# Pico-CRSF.net
KiCad netlist of a schematic drawn in Altium Designer
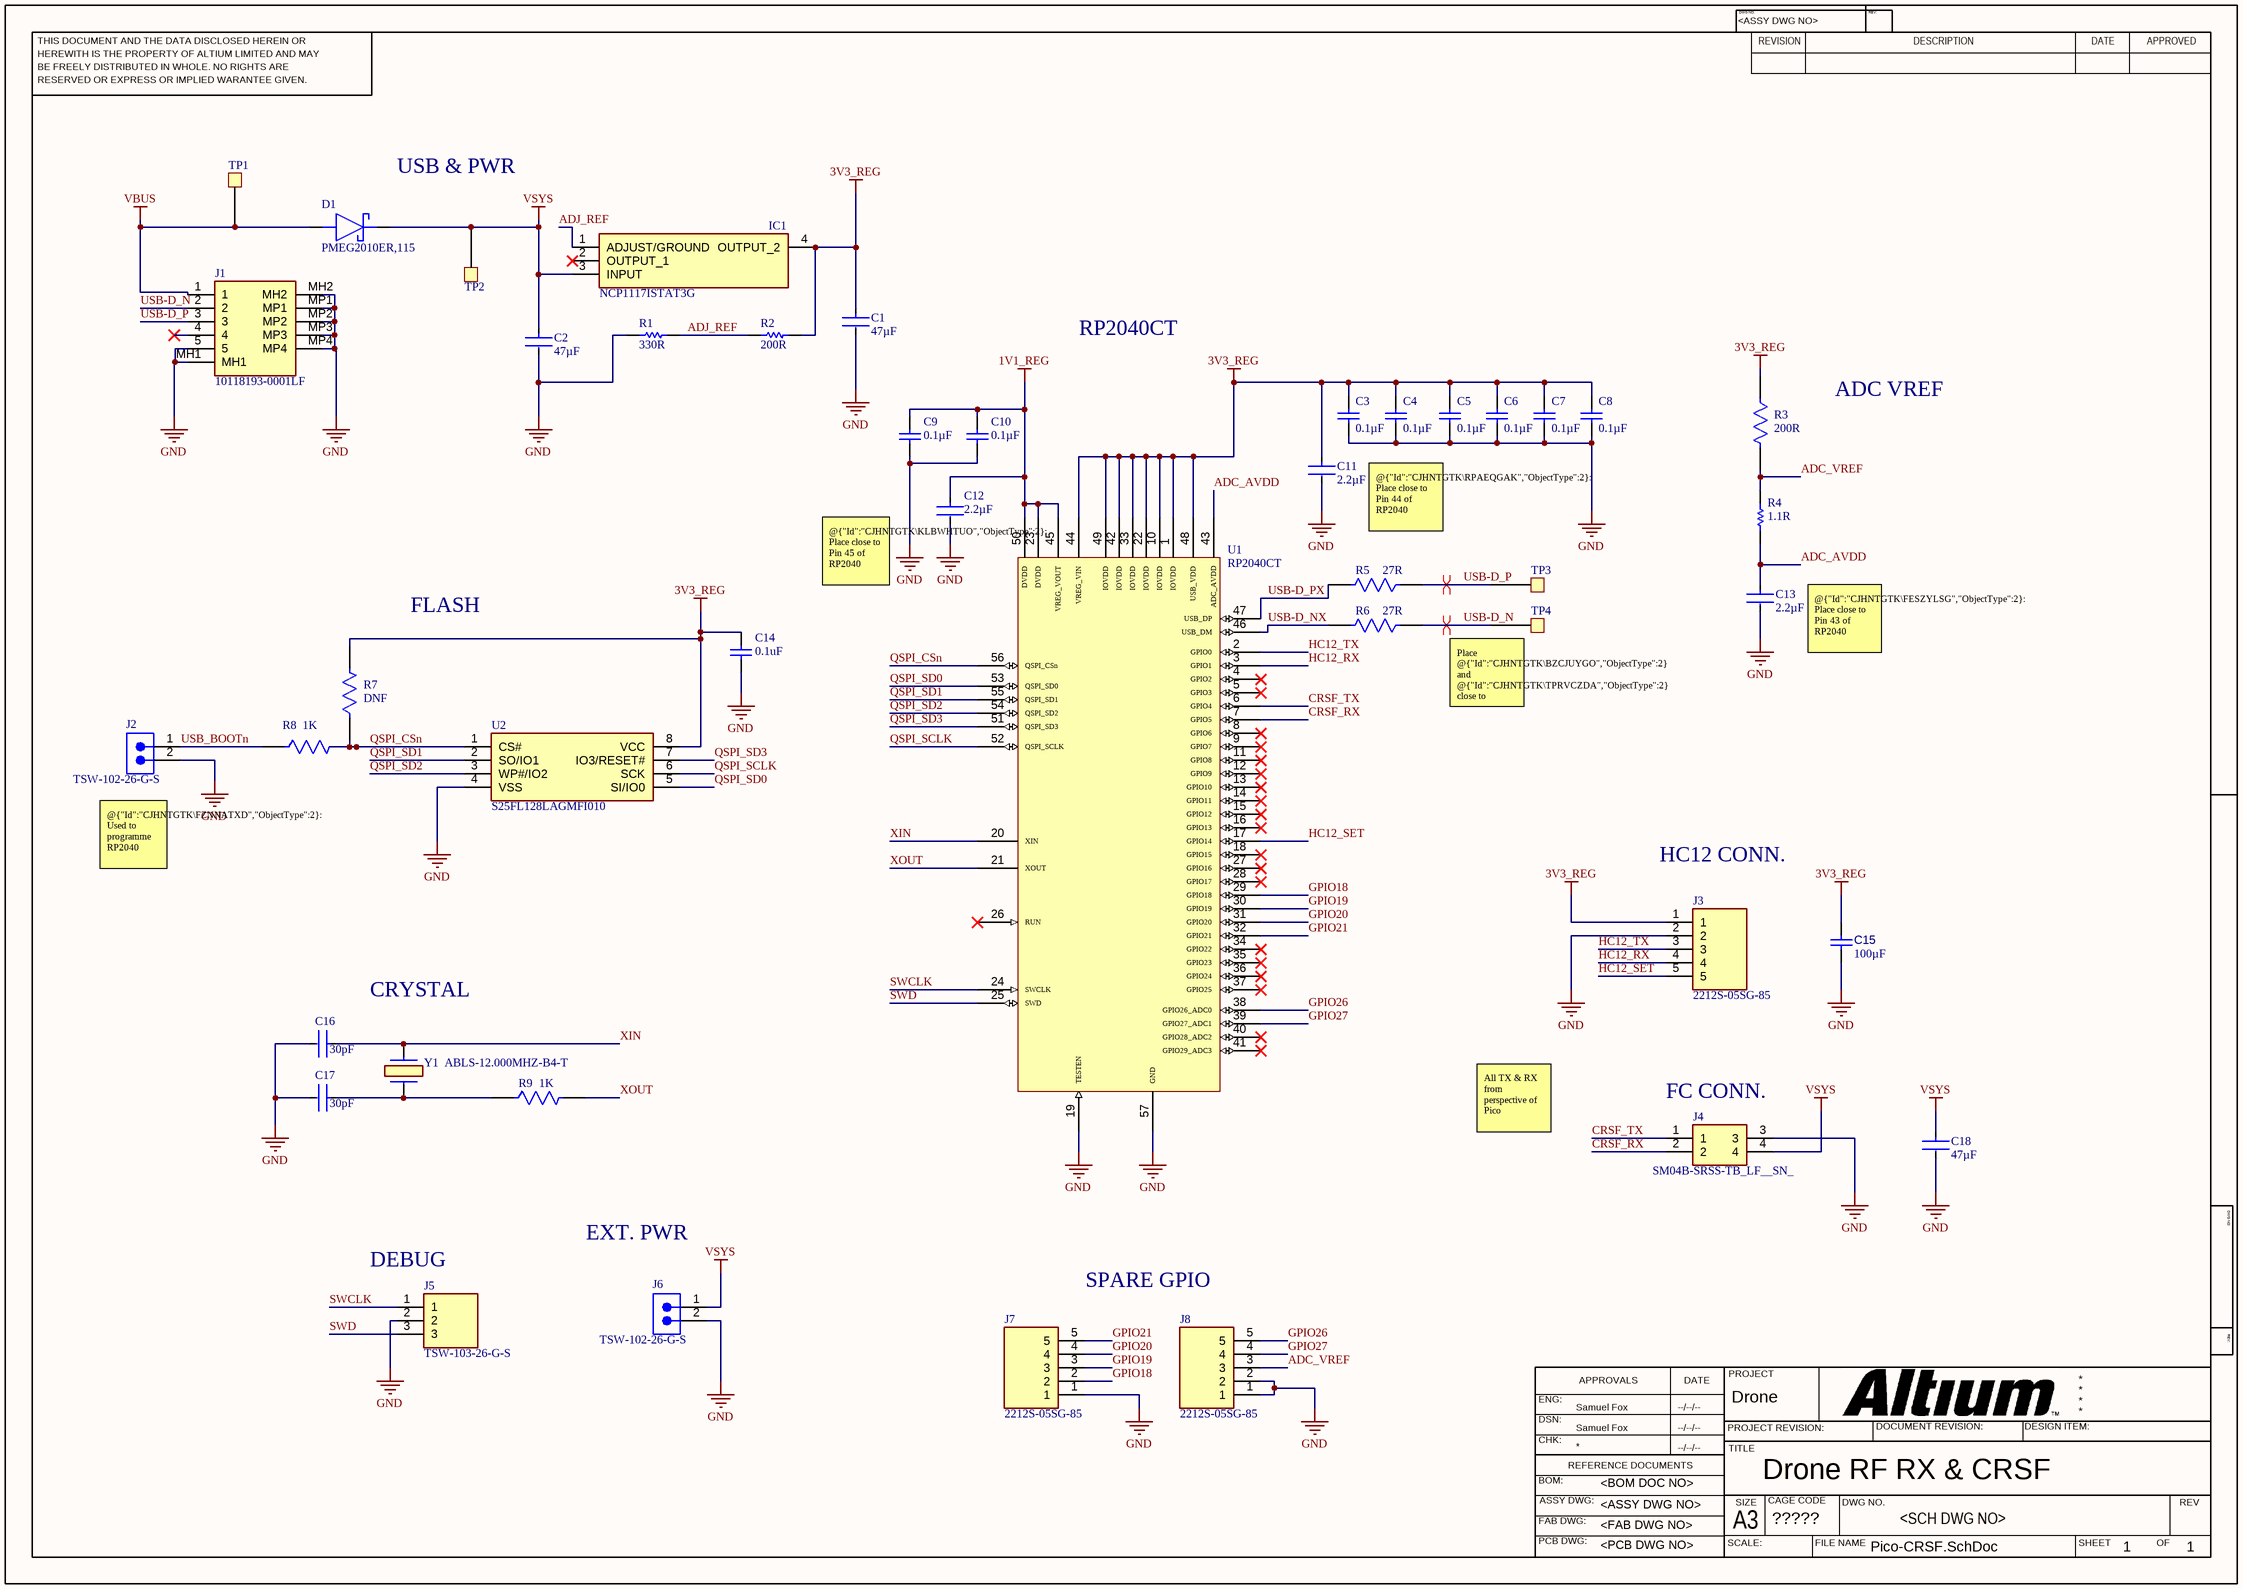
[diagram p0: Pico-CRSF.SchDoc]

(export (version "E")
  (design (tool "Eeschema 10.0.6"))
  (components
    (comp (ref "C1")
      (value "47µF")
      (footprint "FP-GRT21B-0_2-MFG")
      (fields (field (name "Comment") "GRT21BR60J476ME13L"))
      (libsource (lib "Sam Fox") (part "02cd4be3c70576c341d710602a673aa"))
    )
    (comp (ref "C2")
      (value "47µF")
      (footprint "FP-GRT21B-0_2-MFG")
      (fields (field (name "Comment") "GRT21BR60J476ME13L"))
      (libsource (lib "Sam Fox") (part "02cd4be3c70576c341d710602a673aa"))
    )
    (comp (ref "C3")
      (value "0.1µF")
      (footprint "CAPC1005X56X25LL10T15")
      (fields (field (name "Comment") "04026D104KAT2A"))
      (libsource (lib "Sam Fox") (part "CAP"))
    )
    (comp (ref "C4")
      (value "0.1µF")
      (footprint "CAPC1005X56X25LL10T15")
      (fields (field (name "Comment") "04026D104KAT2A"))
      (libsource (lib "Sam Fox") (part "CAP"))
    )
    (comp (ref "C5")
      (value "0.1µF")
      (footprint "CAPC1005X56X25LL10T15")
      (fields (field (name "Comment") "04026D104KAT2A"))
      (libsource (lib "Sam Fox") (part "CAP"))
    )
    (comp (ref "C6")
      (value "0.1µF")
      (footprint "CAPC1005X56X25LL10T15")
      (fields (field (name "Comment") "04026D104KAT2A"))
      (libsource (lib "Sam Fox") (part "CAP"))
    )
    (comp (ref "C7")
      (value "0.1µF")
      (footprint "CAPC1005X56X25LL10T15")
      (fields (field (name "Comment") "04026D104KAT2A"))
      (libsource (lib "Sam Fox") (part "CAP"))
    )
    (comp (ref "C8")
      (value "0.1µF")
      (footprint "CAPC1005X56X25LL10T15")
      (fields (field (name "Comment") "04026D104KAT2A"))
      (libsource (lib "Sam Fox") (part "CAP"))
    )
    (comp (ref "C9")
      (value "0.1µF")
      (footprint "CAPC1005X56X25LL10T15")
      (fields (field (name "Comment") "04026D104KAT2A"))
      (libsource (lib "Sam Fox") (part "CAP"))
    )
    (comp (ref "C10")
      (value "0.1µF")
      (footprint "CAPC1005X56X25LL10T15")
      (fields (field (name "Comment") "04026D104KAT2A"))
      (libsource (lib "Sam Fox") (part "CAP"))
    )
    (comp (ref "C11")
      (value "2.2µF")
      (footprint "FP-GRM155-0_05-MFG")
      (fields (field (name "Comment") "GRM155D80J225ME95D"))
      (libsource (lib "Sam Fox") (part "02cd4be3c70576c341d710602a673aa"))
    )
    (comp (ref "C12")
      (value "2.2µF")
      (footprint "FP-GRM155-0_05-MFG")
      (fields (field (name "Comment") "GRM155D80J225ME95D"))
      (libsource (lib "Sam Fox") (part "02cd4be3c70576c341d710602a673aa"))
    )
    (comp (ref "C13")
      (value "2.2µF")
      (footprint "FP-GRM155-0_05-MFG")
      (fields (field (name "Comment") "GRM155D80J225ME95D"))
      (libsource (lib "Sam Fox") (part "02cd4be3c70576c341d710602a673aa"))
    )
    (comp (ref "C14")
      (value "0.1uF")
      (footprint "CAPC1005X56X25LL10T15")
      (fields (field (name "Comment") "04026D104KAT2A"))
      (libsource (lib "Sam Fox") (part "CAP"))
    )
    (comp (ref "C15")
      (value "100µF")
      (footprint "CAPC3216X16N")
      (fields (field (name "Comment") "CL31A107MQHNNNE"))
      (libsource (lib "Sam Fox") (part "CAP-NP-2"))
    )
    (comp (ref "C16")
      (value "30pF")
      (footprint "FP-GCM155-0_05-IPC_A")
      (fields (field (name "Comment") "GCM1555C1H300JA16D"))
      (libsource (lib "Sam Fox") (part "02cd4be3c70576c341d710602a673aa"))
    )
    (comp (ref "C17")
      (value "30pF")
      (footprint "FP-GCM155-0_05-IPC_A")
      (fields (field (name "Comment") "GCM1555C1H300JA16D"))
      (libsource (lib "Sam Fox") (part "02cd4be3c70576c341d710602a673aa"))
    )
    (comp (ref "C18")
      (value "47µF")
      (footprint "FP-GRT21B-0_2-MFG")
      (fields (field (name "Comment") "GRT21BR60J476ME13L"))
      (libsource (lib "Sam Fox") (part "02cd4be3c70576c341d710602a673aa"))
    )
    (comp (ref "D1")
      (value "PMEG2010ER,115")
      (footprint "SamacSys:PMEG2010ER115")
      (description "Schottky Diode")
      (fields (field (name "MOUSER PART NUMBER") "771-PMEG2010ER115"))
      (libsource (lib "*") (part "PMEG2010ER,115"))
    )
    (comp (ref "IC1")
      (value "NCP1117ISTAT3G")
      (footprint "SamacSys:SOT230P700X180-4N")
      (description "Integrated Circuit")
      (fields (field (name "MOUSER PART NUMBER") "863-NCP1117ISTAT3G"))
      (libsource (lib "*") (part "NCP1117ISTAT3G"))
    )
    (comp (ref "J1")
      (value "10118193-0001LF")
      (footprint "SamacSys:101181930001LF")
      (description "Connector")
      (libsource (lib "*") (part "10118193-0001LF"))
    )
    (comp (ref "J2")
      (value "TSW-102-26-G-S")
      (footprint "SMTC-TSW-102-26-XX-S")
      (description "0.025\" SQ Post Header, Through-hole, Vertical, -55 to 125 degC, 2.54 mm Pitch, 2-Pin, Male, RoHS")
      (fields (field (name "MANUFACTURER") "Samtec"))
      (libsource (lib "Altium Content Vault") (part "SMTC-TSW-102-X-X-S-X"))
    )
    (comp (ref "J3")
      (value "2212S-05SG-85")
      (footprint "SamacSys:RHDR5W74P0X254_1X5_1320X250X850P")
      (description "Connector")
      (libsource (lib "") (part "2212S-05SG-85_1"))
    )
    (comp (ref "J4")
      (value "SM04B-SRSS-TB_LF__SN_")
      (footprint "SamacSys:SM04B-SRSS-TB(LFSN)")
      (description "Connector")
      (fields (field (name "MANUFACTURER_PART_NUMBER") "SM04B-SRSS-TB(LF)(SN)"))
      (libsource (lib "*") (part "SM04B-SRSS-TB_LF__SN_"))
    )
    (comp (ref "J5")
      (value "TSW-103-26-G-S")
      (footprint "SamacSys:TSW-103-XX-YY-S")
      (description "Connector")
      (libsource (lib "*") (part "TSW-103-26-G-S"))
    )
    (comp (ref "J6")
      (value "TSW-102-26-G-S")
      (footprint "SMTC-TSW-102-26-XX-S")
      (description "0.025\" SQ Post Header, Through-hole, Vertical, -55 to 125 degC, 2.54 mm Pitch, 2-Pin, Male, RoHS")
      (fields (field (name "MANUFACTURER") "Samtec"))
      (libsource (lib "Altium Content Vault") (part "SMTC-TSW-102-X-X-S-X"))
    )
    (comp (ref "J7")
      (value "2212S-05SG-85")
      (footprint "SamacSys:RHDR5W74P0X254_1X5_1320X250X850P")
      (description "Connector")
      (libsource (lib "*") (part "2212S-05SG-85"))
    )
    (comp (ref "J8")
      (value "2212S-05SG-85")
      (footprint "SamacSys:RHDR5W74P0X254_1X5_1320X250X850P")
      (description "Connector")
      (libsource (lib "*") (part "2212S-05SG-85"))
    )
    (comp (ref "R1")
      (value "330R")
      (footprint "RESC1005X40X25NL05T10")
      (fields
        (field (name "POWER") "62.5mW")
        (field (name "TOLERANCE") "5%")
        (field (name "Comment") "RC0402JR-07300RL")
      )
      (libsource (lib "Sam Fox") (part "RES"))
    )
    (comp (ref "R2")
      (value "200R")
      (footprint "RESC1005X40X25NL05T10")
      (fields
        (field (name "POWER") "62.5mW")
        (field (name "TOLERANCE") "1%")
        (field (name "Comment") "RC0402FR-07180RL")
      )
      (libsource (lib "Sam Fox") (part "RES"))
    )
    (comp (ref "R3")
      (value "200R")
      (footprint "FP-CR0402-IPC_C")
      (fields
        (field (name "POWER") "62.5mW")
        (field (name "TOLERANCE") "1%")
        (field (name "Comment") "CR0402-FX-2000GLF")
      )
      (libsource (lib "Sam Fox") (part "1029c3af85768c4190bb7ad29bc67b5"))
    )
    (comp (ref "R4")
      (value "1.1R")
      (footprint "RESC1005X40X25NL05T10")
      (fields
        (field (name "POWER") "62.5mW")
        (field (name "TOLERANCE") "1%")
        (field (name "Comment") "RC0402FR-071R")
      )
      (libsource (lib "Sam Fox") (part "RES"))
    )
    (comp (ref "R5")
      (value "27R")
      (footprint "FP-CR0402-IPC_C")
      (fields
        (field (name "POWER") "62.5mW")
        (field (name "TOLERANCE") "1%")
        (field (name "Comment") "CR0402-FX-27R0GLF")
      )
      (libsource (lib "Sam Fox") (part "1029c3af85768c4190bb7ad29bc67b5"))
    )
    (comp (ref "R6")
      (value "27R")
      (footprint "FP-CR0402-IPC_C")
      (fields
        (field (name "POWER") "62.5mW")
        (field (name "TOLERANCE") "1%")
        (field (name "Comment") "CR0402-FX-27R0GLF")
      )
      (libsource (lib "Sam Fox") (part "1029c3af85768c4190bb7ad29bc67b5"))
    )
    (comp (ref "R7")
      (value "DNF")
      (footprint "FP-CR0402-IPC_C")
      (fields (field (name "Comment") "CR0402AFX-1001GAS"))
      (libsource (lib "Sam Fox") (part "1029c3af85768c4190bb7ad29bc67b5"))
    )
    (comp (ref "R8")
      (value "1K")
      (footprint "FP-CR0402-IPC_C")
      (fields (field (name "Comment") "CR0402AFX-1001GAS"))
      (libsource (lib "Sam Fox") (part "1029c3af85768c4190bb7ad29bc67b5"))
    )
    (comp (ref "R9")
      (value "1K")
      (footprint "FP-CR0402-IPC_C")
      (fields (field (name "Comment") "CR0402AFX-1001GAS"))
      (libsource (lib "Sam Fox") (part "1029c3af85768c4190bb7ad29bc67b5"))
    )
    (comp (ref "TP1")
      (value "TestPoint")
      (footprint "TestPoint-Footprint-1")
      (description "Test point for circuit testing.")
      (libsource (lib "") (part "TestPoint_2"))
    )
    (comp (ref "TP2")
      (value "TestPoint")
      (footprint "TestPoint-Footprint-1")
      (description "Test point for circuit testing.")
      (libsource (lib "Sam Fox") (part "TestPoint"))
    )
    (comp (ref "TP3")
      (value "TestPoint")
      (footprint "TestPoint-Footprint-1")
      (description "Test point for circuit testing.")
      (libsource (lib "") (part "TestPoint_1"))
    )
    (comp (ref "TP4")
      (value "TestPoint")
      (footprint "TestPoint-Footprint-1")
      (description "Test point for circuit testing.")
      (libsource (lib "") (part "TestPoint_1"))
    )
    (comp (ref "U1")
      (value "RP2040CT")
      (footprint "QFN40P700X700X90_HS-57N")
      (description "RASPBERRY-PI RP2040CT")
      (libsource (lib "Sam Fox") (part "RP2040CT-Symbol-1"))
    )
    (comp (ref "U2")
      (value "S25FL128LAGMFI010")
      (footprint "SOIC127P800X216-8N")
      (description "CYPRESS SEMICONDUCTOR - S25FL128LAGMFI010 - FLASH MEMORY, 128MBIT, 133MHZ, SOIC-8")
      (libsource (lib "Sam Fox") (part "S25FL128LAGMFI010"))
    )
    (comp (ref "Y1")
      (value "ABLS-12.000MHZ-B4-T")
      (footprint "SamacSys:ABLS")
      (description "Crystal or Oscillator")
      (fields (field (name "MOUSER PART NUMBER") "815-ABLS-12.0M-T"))
      (libsource (lib "*") (part "ABLS-12.000MHZ-B4-T"))
    )
  )
  (nets
    (net (code "1") (name "/ADC_AVDD") (class "Default")
      (node (ref "C13") (pin "1") (pinfunction "1_1") (pintype "passive"))
      (node (ref "R4") (pin "2") (pinfunction "2_2") (pintype "passive"))
      (node (ref "U1") (pin "43") (pinfunction "ADC_AVDD_43") (pintype "power_in"))
    )
    (net (code "2") (name "/ADC_VREF") (class "Default")
      (node (ref "J8") (pin "3") (pinfunction "3_3") (pintype "passive"))
      (node (ref "R3") (pin "2") (pinfunction "2_2") (pintype "passive"))
      (node (ref "R4") (pin "1") (pinfunction "1_1") (pintype "passive"))
    )
    (net (code "3") (name "/ADJ_REF") (class "Default")
      (node (ref "IC1") (pin "1") (pinfunction "ADJUST/GROUND_1") (pintype "passive"))
      (node (ref "R1") (pin "2") (pinfunction "2_2") (pintype "passive"))
      (node (ref "R2") (pin "1") (pinfunction "1_1") (pintype "passive"))
    )
    (net (code "4") (name "/CRSF_RX") (class "Default")
      (node (ref "J4") (pin "2") (pinfunction "2_2") (pintype "passive"))
      (node (ref "U1") (pin "7") (pinfunction "GPIO5_7") (pintype "bidirectional"))
    )
    (net (code "5") (name "/CRSF_TX") (class "Default")
      (node (ref "J4") (pin "1") (pinfunction "1_1") (pintype "passive"))
      (node (ref "U1") (pin "6") (pinfunction "GPIO4_6") (pintype "bidirectional"))
    )
    (net (code "6") (name "/GPIO18") (class "Default")
      (node (ref "J7") (pin "2") (pinfunction "2_2") (pintype "passive"))
      (node (ref "U1") (pin "29") (pinfunction "GPIO18_29") (pintype "bidirectional"))
    )
    (net (code "7") (name "/GPIO19") (class "Default")
      (node (ref "J7") (pin "3") (pinfunction "3_3") (pintype "passive"))
      (node (ref "U1") (pin "30") (pinfunction "GPIO19_30") (pintype "bidirectional"))
    )
    (net (code "8") (name "/GPIO20") (class "Default")
      (node (ref "J7") (pin "4") (pinfunction "4_4") (pintype "passive"))
      (node (ref "U1") (pin "31") (pinfunction "GPIO20_31") (pintype "bidirectional"))
    )
    (net (code "9") (name "/GPIO21") (class "Default")
      (node (ref "J7") (pin "5") (pinfunction "5_5") (pintype "passive"))
      (node (ref "U1") (pin "32") (pinfunction "GPIO21_32") (pintype "bidirectional"))
    )
    (net (code "10") (name "/GPIO26") (class "Default")
      (node (ref "J8") (pin "5") (pinfunction "5_5") (pintype "passive"))
      (node (ref "U1") (pin "38") (pinfunction "GPIO26_ADC0_38") (pintype "bidirectional"))
    )
    (net (code "11") (name "/GPIO27") (class "Default")
      (node (ref "J8") (pin "4") (pinfunction "4_4") (pintype "passive"))
      (node (ref "U1") (pin "39") (pinfunction "GPIO27_ADC1_39") (pintype "bidirectional"))
    )
    (net (code "12") (name "/HC12_RX") (class "Default")
      (node (ref "J3") (pin "4") (pinfunction "4_4") (pintype "passive"))
      (node (ref "U1") (pin "3") (pinfunction "GPIO1_3") (pintype "bidirectional"))
    )
    (net (code "13") (name "/HC12_SET") (class "Default")
      (node (ref "J3") (pin "5") (pinfunction "5_5") (pintype "passive"))
      (node (ref "U1") (pin "17") (pinfunction "GPIO14_17") (pintype "bidirectional"))
    )
    (net (code "14") (name "/HC12_TX") (class "Default")
      (node (ref "J3") (pin "3") (pinfunction "3_3") (pintype "passive"))
      (node (ref "U1") (pin "2") (pinfunction "GPIO0_2") (pintype "bidirectional"))
    )
    (net (code "15") (name "/QSPI_CSn") (class "Default")
      (node (ref "R7") (pin "1") (pinfunction "1_1") (pintype "passive"))
      (node (ref "R8") (pin "2") (pinfunction "2_2") (pintype "passive"))
      (node (ref "U1") (pin "56") (pinfunction "QSPI_CSn_56") (pintype "bidirectional"))
      (node (ref "U2") (pin "1") (pinfunction "CS#_1") (pintype "passive"))
    )
    (net (code "16") (name "/QSPI_SCLK") (class "Default")
      (node (ref "U1") (pin "52") (pinfunction "QSPI_SCLK_52") (pintype "bidirectional"))
      (node (ref "U2") (pin "6") (pinfunction "SCK_6") (pintype "passive"))
    )
    (net (code "17") (name "/QSPI_SD0") (class "Default")
      (node (ref "U1") (pin "53") (pinfunction "QSPI_SD0_53") (pintype "bidirectional"))
      (node (ref "U2") (pin "5") (pinfunction "SI/IO0_5") (pintype "passive"))
    )
    (net (code "18") (name "/QSPI_SD1") (class "Default")
      (node (ref "U1") (pin "55") (pinfunction "QSPI_SD1_55") (pintype "bidirectional"))
      (node (ref "U2") (pin "2") (pinfunction "SO/IO1_2") (pintype "passive"))
    )
    (net (code "19") (name "/QSPI_SD2") (class "Default")
      (node (ref "U1") (pin "54") (pinfunction "QSPI_SD2_54") (pintype "bidirectional"))
      (node (ref "U2") (pin "3") (pinfunction "WP#/IO2_3") (pintype "passive"))
    )
    (net (code "20") (name "/QSPI_SD3") (class "Default")
      (node (ref "U1") (pin "51") (pinfunction "QSPI_SD3_51") (pintype "bidirectional"))
      (node (ref "U2") (pin "7") (pinfunction "IO3/RESET#_7") (pintype "passive"))
    )
    (net (code "21") (name "/SWCLK") (class "Default")
      (node (ref "J5") (pin "1") (pinfunction "1_1") (pintype "passive"))
      (node (ref "U1") (pin "24") (pinfunction "SWCLK_24") (pintype "input"))
    )
    (net (code "22") (name "/SWD") (class "Default")
      (node (ref "J5") (pin "3") (pinfunction "3_3") (pintype "passive"))
      (node (ref "U1") (pin "25") (pinfunction "SWD_25") (pintype "bidirectional"))
    )
    (net (code "23") (name "/USB-D_N") (class "Default")
      (node (ref "J1") (pin "2") (pinfunction "2_2") (pintype "passive"))
      (node (ref "R6") (pin "1") (pinfunction "1_1") (pintype "passive"))
      (node (ref "TP4") (pin "1") (pintype "passive"))
    )
    (net (code "24") (name "/USB-D_NX") (class "Default")
      (node (ref "R6") (pin "2") (pinfunction "2_2") (pintype "passive"))
      (node (ref "U1") (pin "46") (pinfunction "USB_DM_46") (pintype "bidirectional"))
    )
    (net (code "25") (name "/USB-D_P") (class "Default")
      (node (ref "J1") (pin "3") (pinfunction "3_3") (pintype "passive"))
      (node (ref "R5") (pin "1") (pinfunction "1_1") (pintype "passive"))
      (node (ref "TP3") (pin "1") (pintype "passive"))
    )
    (net (code "26") (name "/USB-D_PX") (class "Default")
      (node (ref "R5") (pin "2") (pinfunction "2_2") (pintype "passive"))
      (node (ref "U1") (pin "47") (pinfunction "USB_DP_47") (pintype "bidirectional"))
    )
    (net (code "27") (name "/USB_BOOTn") (class "Default")
      (node (ref "J2") (pin "1") (pinfunction "1_1") (pintype "passive"))
      (node (ref "R8") (pin "1") (pinfunction "1_1") (pintype "passive"))
    )
    (net (code "28") (name "/XIN") (class "Default")
      (node (ref "C16") (pin "1") (pinfunction "1_1") (pintype "passive"))
      (node (ref "U1") (pin "20") (pinfunction "XIN_20") (pintype "passive"))
      (node (ref "Y1") (pin "1") (pinfunction "1_1") (pintype "passive"))
    )
    (net (code "29") (name "/XOUT") (class "Default")
      (node (ref "R9") (pin "2") (pinfunction "2_2") (pintype "passive"))
      (node (ref "U1") (pin "21") (pinfunction "XOUT_21") (pintype "passive"))
    )
    (net (code "30") (name "1V1_REG") (class "Default")
      (node (ref "C10") (pin "1") (pinfunction "1_1") (pintype "passive"))
      (node (ref "C12") (pin "1") (pinfunction "1_1") (pintype "passive"))
      (node (ref "C9") (pin "1") (pinfunction "1_1") (pintype "passive"))
      (node (ref "U1") (pin "23") (pinfunction "DVDD_23") (pintype "power_in"))
      (node (ref "U1") (pin "45") (pinfunction "VREG_VOUT_45") (pintype "power_in"))
      (node (ref "U1") (pin "50") (pinfunction "DVDD_50") (pintype "power_in"))
    )
    (net (code "31") (name "3V3_REG") (class "Default")
      (node (ref "C1") (pin "1") (pinfunction "1_1") (pintype "passive"))
      (node (ref "C11") (pin "1") (pinfunction "1_1") (pintype "passive"))
      (node (ref "C14") (pin "1") (pinfunction "1_1") (pintype "passive"))
      (node (ref "C15") (pin "1") (pinfunction "1_1") (pintype "passive"))
      (node (ref "C3") (pin "1") (pinfunction "1_1") (pintype "passive"))
      (node (ref "C4") (pin "1") (pinfunction "1_1") (pintype "passive"))
      (node (ref "C5") (pin "1") (pinfunction "1_1") (pintype "passive"))
      (node (ref "C6") (pin "1") (pinfunction "1_1") (pintype "passive"))
      (node (ref "C7") (pin "1") (pinfunction "1_1") (pintype "passive"))
      (node (ref "C8") (pin "1") (pinfunction "1_1") (pintype "passive"))
      (node (ref "IC1") (pin "4") (pinfunction "OUTPUT_2_4") (pintype "passive"))
      (node (ref "J3") (pin "1") (pinfunction "1_1") (pintype "passive"))
      (node (ref "R2") (pin "2") (pinfunction "2_2") (pintype "passive"))
      (node (ref "R3") (pin "1") (pinfunction "1_1") (pintype "passive"))
      (node (ref "R7") (pin "2") (pinfunction "2_2") (pintype "passive"))
      (node (ref "U1") (pin "1") (pinfunction "IOVDD_1") (pintype "power_in"))
      (node (ref "U1") (pin "10") (pinfunction "IOVDD_10") (pintype "power_in"))
      (node (ref "U1") (pin "22") (pinfunction "IOVDD_22") (pintype "power_in"))
      (node (ref "U1") (pin "33") (pinfunction "IOVDD_33") (pintype "power_in"))
      (node (ref "U1") (pin "42") (pinfunction "IOVDD_42") (pintype "power_in"))
      (node (ref "U1") (pin "44") (pinfunction "VREG_VIN_44") (pintype "power_in"))
      (node (ref "U1") (pin "48") (pinfunction "USB_VDD_48") (pintype "power_in"))
      (node (ref "U1") (pin "49") (pinfunction "IOVDD_49") (pintype "power_in"))
      (node (ref "U2") (pin "8") (pinfunction "VCC_8") (pintype "passive"))
    )
    (net (code "32") (name "GND") (class "Default")
      (node (ref "C1") (pin "2") (pinfunction "2_2") (pintype "passive"))
      (node (ref "C10") (pin "2") (pinfunction "2_2") (pintype "passive"))
      (node (ref "C11") (pin "2") (pinfunction "2_2") (pintype "passive"))
      (node (ref "C12") (pin "2") (pinfunction "2_2") (pintype "passive"))
      (node (ref "C13") (pin "2") (pinfunction "2_2") (pintype "passive"))
      (node (ref "C14") (pin "2") (pinfunction "2_2") (pintype "passive"))
      (node (ref "C15") (pin "2") (pinfunction "2_2") (pintype "passive"))
      (node (ref "C16") (pin "2") (pinfunction "2_2") (pintype "passive"))
      (node (ref "C17") (pin "2") (pinfunction "2_2") (pintype "passive"))
      (node (ref "C18") (pin "2") (pinfunction "2_2") (pintype "passive"))
      (node (ref "C2") (pin "2") (pinfunction "2_2") (pintype "passive"))
      (node (ref "C3") (pin "2") (pinfunction "2_2") (pintype "passive"))
      (node (ref "C4") (pin "2") (pinfunction "2_2") (pintype "passive"))
      (node (ref "C5") (pin "2") (pinfunction "2_2") (pintype "passive"))
      (node (ref "C6") (pin "2") (pinfunction "2_2") (pintype "passive"))
      (node (ref "C7") (pin "2") (pinfunction "2_2") (pintype "passive"))
      (node (ref "C8") (pin "2") (pinfunction "2_2") (pintype "passive"))
      (node (ref "C9") (pin "2") (pinfunction "2_2") (pintype "passive"))
      (node (ref "J1") (pin "5") (pinfunction "5_5") (pintype "passive"))
      (node (ref "J1") (pin "MH1") (pinfunction "MH1_MH1") (pintype "passive"))
      (node (ref "J1") (pin "MH2") (pinfunction "MH2_MH2") (pintype "passive"))
      (node (ref "J1") (pin "MP1") (pinfunction "MP1_MP1") (pintype "passive"))
      (node (ref "J1") (pin "MP2") (pinfunction "MP2_MP2") (pintype "passive"))
      (node (ref "J1") (pin "MP3") (pinfunction "MP3_MP3") (pintype "passive"))
      (node (ref "J1") (pin "MP4") (pinfunction "MP4_MP4") (pintype "passive"))
      (node (ref "J2") (pin "2") (pinfunction "2_2") (pintype "passive"))
      (node (ref "J3") (pin "2") (pinfunction "2_2") (pintype "passive"))
      (node (ref "J4") (pin "3") (pinfunction "3_3") (pintype "passive"))
      (node (ref "J5") (pin "2") (pinfunction "2_2") (pintype "passive"))
      (node (ref "J6") (pin "2") (pinfunction "2_2") (pintype "passive"))
      (node (ref "J7") (pin "1") (pinfunction "1_1") (pintype "passive"))
      (node (ref "J8") (pin "1") (pinfunction "1_1") (pintype "passive"))
      (node (ref "J8") (pin "2") (pinfunction "2_2") (pintype "passive"))
      (node (ref "R1") (pin "1") (pinfunction "1_1") (pintype "passive"))
      (node (ref "U1") (pin "19") (pinfunction "TESTEN_19") (pintype "input"))
      (node (ref "U1") (pin "57") (pinfunction "GND_57") (pintype "power_in"))
      (node (ref "U2") (pin "4") (pinfunction "VSS_4") (pintype "passive"))
    )
    (net (code "33") (name "Net-(C17-Pad1)") (class "Default")
      (node (ref "C17") (pin "1") (pinfunction "1_1") (pintype "passive"))
      (node (ref "R9") (pin "1") (pinfunction "1_1") (pintype "passive"))
      (node (ref "Y1") (pin "2") (pinfunction "2_2") (pintype "passive"))
    )
    (net (code "34") (name "VBUS") (class "Default")
      (node (ref "D1") (pin "2") (pinfunction "A_2") (pintype "passive"))
      (node (ref "J1") (pin "1") (pinfunction "1_1") (pintype "passive"))
      (node (ref "TP1") (pin "1") (pintype "passive"))
    )
    (net (code "35") (name "VSYS") (class "Default")
      (node (ref "C18") (pin "1") (pinfunction "1_1") (pintype "passive"))
      (node (ref "C2") (pin "1") (pinfunction "1_1") (pintype "passive"))
      (node (ref "D1") (pin "1") (pinfunction "K_1") (pintype "passive"))
      (node (ref "IC1") (pin "3") (pinfunction "INPUT_3") (pintype "passive"))
      (node (ref "J4") (pin "4") (pinfunction "4_4") (pintype "passive"))
      (node (ref "J6") (pin "1") (pinfunction "1_1") (pintype "passive"))
      (node (ref "TP2") (pin "1") (pintype "passive"))
    )
    (net (code "36") (name "unconnected-(IC1-OUTPUT_1-Pad2)") (class "Default")
      (node (ref "IC1") (pin "2") (pinfunction "OUTPUT_1_2") (pintype "passive+no_connect"))
    )
    (net (code "37") (name "unconnected-(J1-Pad4)") (class "Default")
      (node (ref "J1") (pin "4") (pinfunction "4_4") (pintype "passive+no_connect"))
    )
    (net (code "38") (name "unconnected-(U1-GPIO2-Pad4)") (class "Default")
      (node (ref "U1") (pin "4") (pinfunction "GPIO2_4") (pintype "bidirectional+no_connect"))
    )
    (net (code "39") (name "unconnected-(U1-GPIO3-Pad5)") (class "Default")
      (node (ref "U1") (pin "5") (pinfunction "GPIO3_5") (pintype "bidirectional+no_connect"))
    )
    (net (code "40") (name "unconnected-(U1-GPIO6-Pad8)") (class "Default")
      (node (ref "U1") (pin "8") (pinfunction "GPIO6_8") (pintype "bidirectional+no_connect"))
    )
    (net (code "41") (name "unconnected-(U1-GPIO7-Pad9)") (class "Default")
      (node (ref "U1") (pin "9") (pinfunction "GPIO7_9") (pintype "bidirectional+no_connect"))
    )
    (net (code "42") (name "unconnected-(U1-GPIO8-Pad11)") (class "Default")
      (node (ref "U1") (pin "11") (pinfunction "GPIO8_11") (pintype "bidirectional+no_connect"))
    )
    (net (code "43") (name "unconnected-(U1-GPIO9-Pad12)") (class "Default")
      (node (ref "U1") (pin "12") (pinfunction "GPIO9_12") (pintype "bidirectional+no_connect"))
    )
    (net (code "44") (name "unconnected-(U1-GPIO10-Pad13)") (class "Default")
      (node (ref "U1") (pin "13") (pinfunction "GPIO10_13") (pintype "bidirectional+no_connect"))
    )
    (net (code "45") (name "unconnected-(U1-GPIO11-Pad14)") (class "Default")
      (node (ref "U1") (pin "14") (pinfunction "GPIO11_14") (pintype "bidirectional+no_connect"))
    )
    (net (code "46") (name "unconnected-(U1-GPIO12-Pad15)") (class "Default")
      (node (ref "U1") (pin "15") (pinfunction "GPIO12_15") (pintype "bidirectional+no_connect"))
    )
    (net (code "47") (name "unconnected-(U1-GPIO13-Pad16)") (class "Default")
      (node (ref "U1") (pin "16") (pinfunction "GPIO13_16") (pintype "bidirectional+no_connect"))
    )
    (net (code "48") (name "unconnected-(U1-GPIO15-Pad18)") (class "Default")
      (node (ref "U1") (pin "18") (pinfunction "GPIO15_18") (pintype "bidirectional+no_connect"))
    )
    (net (code "49") (name "unconnected-(U1-GPIO16-Pad27)") (class "Default")
      (node (ref "U1") (pin "27") (pinfunction "GPIO16_27") (pintype "bidirectional+no_connect"))
    )
    (net (code "50") (name "unconnected-(U1-GPIO17-Pad28)") (class "Default")
      (node (ref "U1") (pin "28") (pinfunction "GPIO17_28") (pintype "bidirectional+no_connect"))
    )
    (net (code "51") (name "unconnected-(U1-GPIO22-Pad34)") (class "Default")
      (node (ref "U1") (pin "34") (pinfunction "GPIO22_34") (pintype "bidirectional+no_connect"))
    )
    (net (code "52") (name "unconnected-(U1-GPIO23-Pad35)") (class "Default")
      (node (ref "U1") (pin "35") (pinfunction "GPIO23_35") (pintype "bidirectional+no_connect"))
    )
    (net (code "53") (name "unconnected-(U1-GPIO24-Pad36)") (class "Default")
      (node (ref "U1") (pin "36") (pinfunction "GPIO24_36") (pintype "bidirectional+no_connect"))
    )
    (net (code "54") (name "unconnected-(U1-GPIO25-Pad37)") (class "Default")
      (node (ref "U1") (pin "37") (pinfunction "GPIO25_37") (pintype "bidirectional+no_connect"))
    )
    (net (code "55") (name "unconnected-(U1-GPIO28_ADC2-Pad40)") (class "Default")
      (node (ref "U1") (pin "40") (pinfunction "GPIO28_ADC2_40") (pintype "bidirectional+no_connect"))
    )
    (net (code "56") (name "unconnected-(U1-GPIO29_ADC3-Pad41)") (class "Default")
      (node (ref "U1") (pin "41") (pinfunction "GPIO29_ADC3_41") (pintype "bidirectional+no_connect"))
    )
    (net (code "57") (name "unconnected-(U1-RUN-Pad26)") (class "Default")
      (node (ref "U1") (pin "26") (pinfunction "RUN_26") (pintype "input+no_connect"))
    )
  )
)
